# 3v3_power.net
KiCad netlist of a schematic drawn in EAGLE
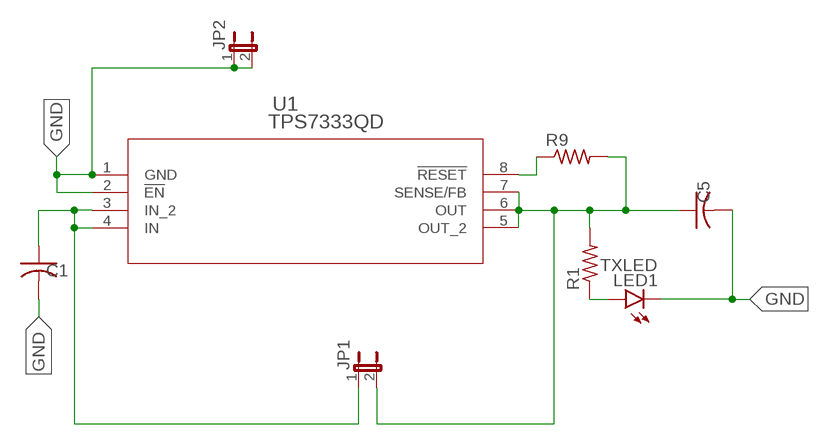
[diagram p0: schematic, sheet 1]

(export (version "E")
  (design (tool "Eeschema 10.0.6"))
  (components
    (comp (ref "C1")
      (value "C-USC1206")
      (footprint "eagle-import:C1206")
      (libsource (lib "eagle-import") (part "C-USC1206"))
    )
    (comp (ref "C5")
      (value "C-USC1206")
      (footprint "eagle-import:C1206")
      (libsource (lib "eagle-import") (part "C-USC1206"))
    )
    (comp (ref "JP1")
      (value "JP1E")
      (footprint "eagle-import:JP1")
      (libsource (lib "eagle-import") (part "JP1E"))
    )
    (comp (ref "JP2")
      (value "JP1E")
      (footprint "eagle-import:JP1")
      (libsource (lib "eagle-import") (part "JP1E"))
    )
    (comp (ref "LED1")
      (value "TXLED")
      (footprint "eagle-import:CHIPLED_1206")
      (libsource (lib "eagle-import") (part "LEDCHIPLED_1206"))
    )
    (comp (ref "R1")
      (value "R-US_R1206")
      (footprint "eagle-import:R1206")
      (libsource (lib "eagle-import") (part "R-US_R1206"))
    )
    (comp (ref "R9")
      (value "R-US_R1206")
      (footprint "eagle-import:R1206")
      (libsource (lib "eagle-import") (part "R-US_R1206"))
    )
    (comp (ref "U1")
      (value "TPS7333QD")
      (footprint "eagle-import:D8")
      (libsource (lib "eagle-import") (part "TPS7333QD"))
    )
  )
  (nets
    (net (code "1") (name "GND") (class "Default")
      (node (ref "C1") (pin "2") (pinfunction "2_2") (pintype "passive"))
      (node (ref "C5") (pin "2") (pinfunction "2_2") (pintype "passive"))
      (node (ref "JP2") (pin "1") (pinfunction "1_1") (pintype "passive"))
      (node (ref "JP2") (pin "2") (pinfunction "2_2") (pintype "passive"))
      (node (ref "LED1") (pin "C") (pinfunction "C_C") (pintype "passive"))
      (node (ref "U1") (pin "1") (pinfunction "GND_1") (pintype "power_in"))
      (node (ref "U1") (pin "2") (pinfunction "~{EN}_2") (pintype "passive"))
    )
    (net (code "2") (name "Net-(LED1-PadA)") (class "Default")
      (node (ref "LED1") (pin "A") (pinfunction "A_A") (pintype "passive"))
      (node (ref "R1") (pin "1") (pinfunction "1_1") (pintype "passive"))
    )
    (net (code "3") (name "Net-(U1-IN)") (class "Default")
      (node (ref "C1") (pin "1") (pinfunction "1_1") (pintype "passive"))
      (node (ref "JP1") (pin "1") (pinfunction "1_1") (pintype "passive"))
      (node (ref "U1") (pin "3") (pinfunction "IN_2_3") (pintype "input"))
      (node (ref "U1") (pin "4") (pinfunction "IN_4") (pintype "input"))
    )
    (net (code "4") (name "Net-(U1-OUT)") (class "Default")
      (node (ref "C5") (pin "1") (pinfunction "1_1") (pintype "passive"))
      (node (ref "JP1") (pin "2") (pinfunction "2_2") (pintype "passive"))
      (node (ref "R1") (pin "2") (pinfunction "2_2") (pintype "passive"))
      (node (ref "R9") (pin "2") (pinfunction "2_2") (pintype "passive"))
      (node (ref "U1") (pin "5") (pinfunction "OUT_2_5") (pintype "output"))
      (node (ref "U1") (pin "6") (pinfunction "OUT_6") (pintype "output"))
      (node (ref "U1") (pin "7") (pinfunction "SENSE/FB_7") (pintype "bidirectional"))
    )
    (net (code "5") (name "Net-(U1-~{RESET})") (class "Default")
      (node (ref "R9") (pin "1") (pinfunction "1_1") (pintype "passive"))
      (node (ref "U1") (pin "8") (pinfunction "~{RESET}_8") (pintype "passive"))
    )
  )
)
